# CW_demcheva_ControlBoard_Sh1.net
KiCad netlist of a schematic drawn in Altium Designer
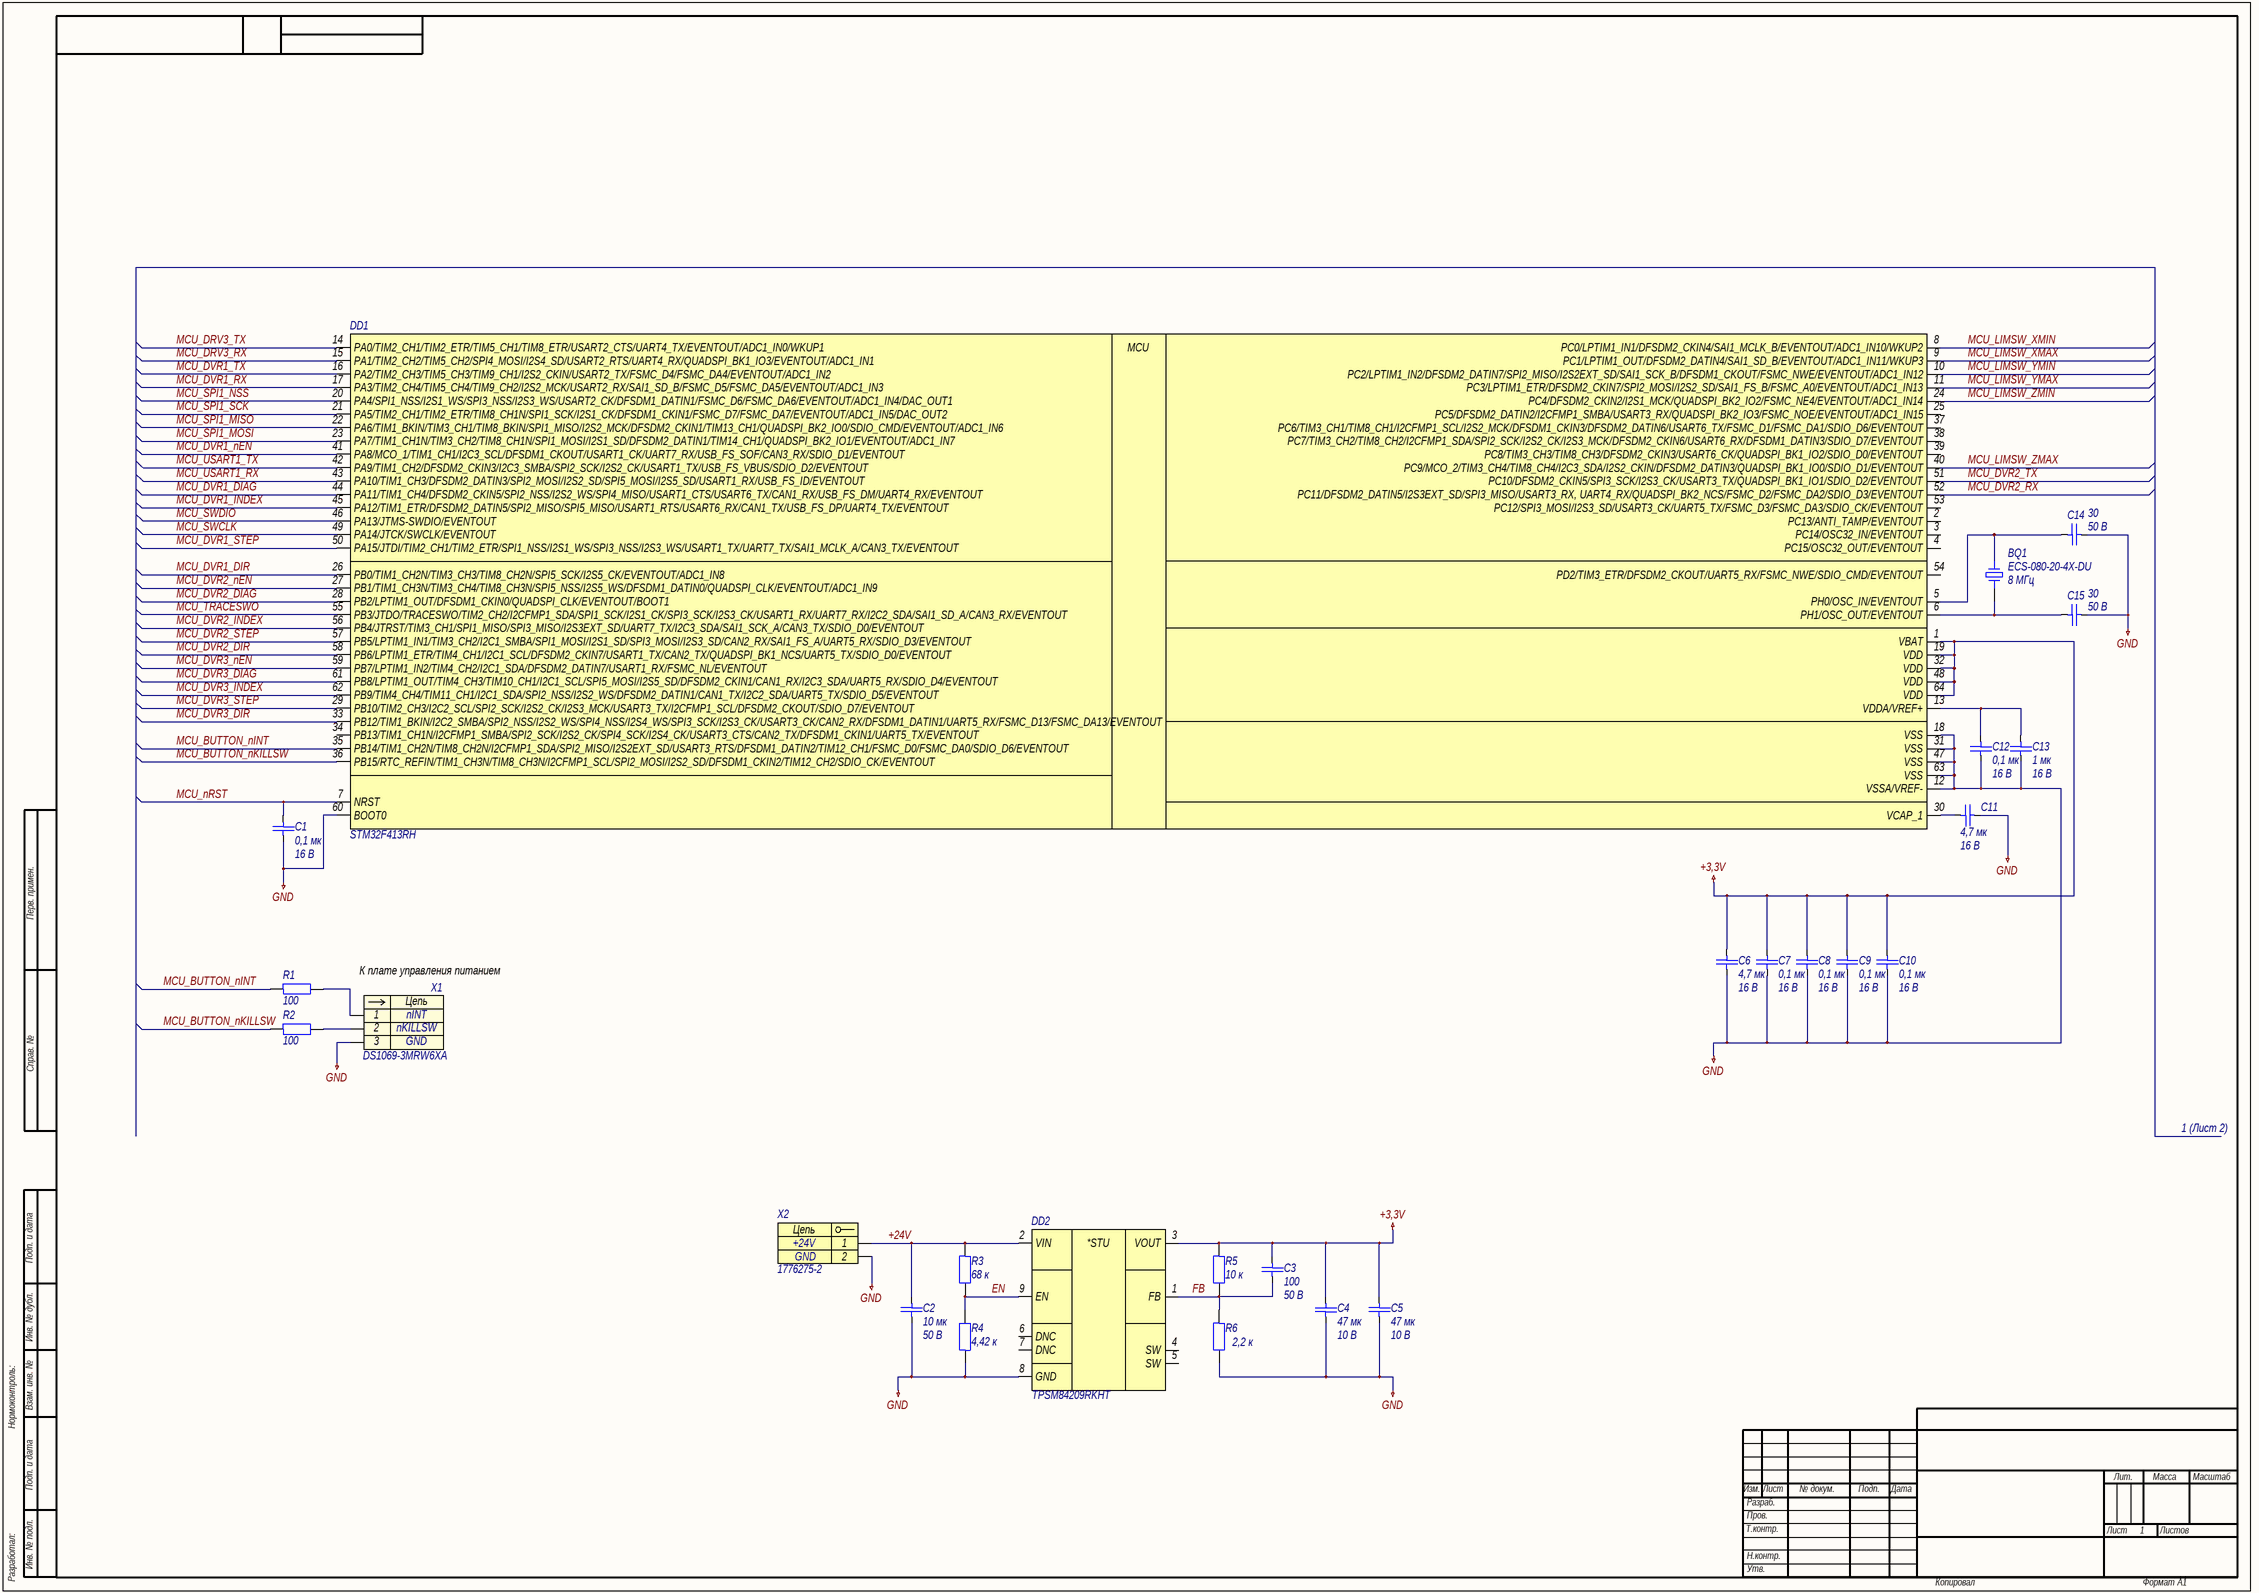
[diagram p0: CW_demcheva_ControlBoard_Sh1.SchDoc]

(export (version "E")
  (design (tool "Eeschema 10.0.6"))
  (components
    (comp (ref "BQ1")
      (value "ECS-080-20-4X-DU")
      (footprint "HC-49/US")
      (description "=Описание")
      (fields (field (name "ЧАСТОТA") "8 МГц"))
      (libsource (lib "Database_Students") (part "RESONATOR-COMMON"))
    )
    (comp (ref "C1")
      (value "0,1 мк")
      (footprint "C0603")
      (description "=Описание")
      (fields (field (name "НАПРЯЖЕНИЕ") "16 В"))
      (libsource (lib "Database_Students") (part "CAPACITOR-NONPOLAR"))
    )
    (comp (ref "C2")
      (value "10 мк")
      (footprint "C0805")
      (description "=Описание")
      (fields (field (name "НАПРЯЖЕНИЕ") "50 В"))
      (libsource (lib "Database_Students") (part "CAPACITOR-NONPOLAR"))
    )
    (comp (ref "C3")
      (value "100")
      (footprint "C0603")
      (description "=Описание")
      (fields (field (name "НАПРЯЖЕНИЕ") "50 В"))
      (libsource (lib "Database_Students") (part "CAPACITOR-NONPOLAR"))
    )
    (comp (ref "C4")
      (value "47 мк")
      (footprint "C0805")
      (description "=Описание")
      (fields (field (name "НАПРЯЖЕНИЕ") "10 В"))
      (libsource (lib "Database_Students") (part "CAPACITOR-NONPOLAR"))
    )
    (comp (ref "C5")
      (value "47 мк")
      (footprint "C0805")
      (description "=Описание")
      (fields (field (name "НАПРЯЖЕНИЕ") "10 В"))
      (libsource (lib "Database_Students") (part "CAPACITOR-NONPOLAR"))
    )
    (comp (ref "C6")
      (value "4,7 мк")
      (footprint "C0805")
      (description "=Описание")
      (fields (field (name "НАПРЯЖЕНИЕ") "16 В"))
      (libsource (lib "Database_Students") (part "CAPACITOR-NONPOLAR"))
    )
    (comp (ref "C7")
      (value "0,1 мк")
      (footprint "C0603")
      (description "=Описание")
      (fields (field (name "НАПРЯЖЕНИЕ") "16 В"))
      (libsource (lib "Database_Students") (part "CAPACITOR-NONPOLAR"))
    )
    (comp (ref "C8")
      (value "0,1 мк")
      (footprint "C0603")
      (description "=Описание")
      (fields (field (name "НАПРЯЖЕНИЕ") "16 В"))
      (libsource (lib "Database_Students") (part "CAPACITOR-NONPOLAR"))
    )
    (comp (ref "C9")
      (value "0,1 мк")
      (footprint "C0603")
      (description "=Описание")
      (fields (field (name "НАПРЯЖЕНИЕ") "16 В"))
      (libsource (lib "Database_Students") (part "CAPACITOR-NONPOLAR"))
    )
    (comp (ref "C10")
      (value "0,1 мк")
      (footprint "C0603")
      (description "=Описание")
      (fields (field (name "НАПРЯЖЕНИЕ") "16 В"))
      (libsource (lib "Database_Students") (part "CAPACITOR-NONPOLAR"))
    )
    (comp (ref "C11")
      (value "4,7 мк")
      (footprint "C0805")
      (description "=Описание")
      (fields (field (name "НАПРЯЖЕНИЕ") "16 В"))
      (libsource (lib "Database_Students") (part "CAPACITOR-NONPOLAR"))
    )
    (comp (ref "C12")
      (value "0,1 мк")
      (footprint "C0603")
      (description "=Описание")
      (fields (field (name "НАПРЯЖЕНИЕ") "16 В"))
      (libsource (lib "Database_Students") (part "CAPACITOR-NONPOLAR"))
    )
    (comp (ref "C13")
      (value "1 мк")
      (footprint "C0603")
      (description "=Описание")
      (fields (field (name "НАПРЯЖЕНИЕ") "16 В"))
      (libsource (lib "Database_Students") (part "CAPACITOR-NONPOLAR"))
    )
    (comp (ref "C14")
      (value "30")
      (footprint "C0603")
      (description "=Описание")
      (fields (field (name "НАПРЯЖЕНИЕ") "50 В"))
      (libsource (lib "Database_Students") (part "CAPACITOR-NONPOLAR"))
    )
    (comp (ref "C15")
      (value "30")
      (footprint "C0603")
      (description "=Описание")
      (fields (field (name "НАПРЯЖЕНИЕ") "50 В"))
      (libsource (lib "Database_Students") (part "CAPACITOR-NONPOLAR"))
    )
    (comp (ref "DD1")
      (value "STM32F413RH")
      (footprint "LQFP-64-P50-1000X1000X160-L60X22")
      (description "=Описание")
      (libsource (lib "Database_Students") (part "STM32F413RHT6"))
    )
    (comp (ref "DD2")
      (value "TPSM84209RKHT")
      (footprint "QFN-FCMOD-9-P65-450X400X210")
      (description "=Описание")
      (libsource (lib "Database_Students") (part "TPSM84209RKHT"))
    )
    (comp (ref "R1")
      (value "100")
      (footprint "R0603")
      (description "=Описание")
      (libsource (lib "Database_Students") (part "RESISTOR-COMMON"))
    )
    (comp (ref "R2")
      (value "100")
      (footprint "R0603")
      (description "=Описание")
      (libsource (lib "Database_Students") (part "RESISTOR-COMMON"))
    )
    (comp (ref "R3")
      (value "68 к")
      (footprint "R0603")
      (description "=Описание")
      (libsource (lib "Database_Students") (part "RESISTOR-COMMON"))
    )
    (comp (ref "R4")
      (value "4,42 к")
      (footprint "R0603")
      (description "=Описание")
      (libsource (lib "Database_Students") (part "RESISTOR-COMMON"))
    )
    (comp (ref "R5")
      (value "10 к")
      (footprint "R0603")
      (description "=Описание")
      (libsource (lib "Database_Students") (part "RESISTOR-COMMON"))
    )
    (comp (ref "R6")
      (value "2,2 к")
      (footprint "R0603")
      (description "=Описание")
      (libsource (lib "Database_Students") (part "RESISTOR-COMMON"))
    )
    (comp (ref "X1")
      (value "DS1069-3MRW6XA")
      (footprint "DS1069-3MRW6XA")
      (description "=Описание")
      (libsource (lib "Database_Students") (part "HEADER-3-PLG"))
    )
    (comp (ref "X2")
      (value "1776275-2")
      (footprint "1776275-2")
      (description "=Описание")
      (libsource (lib "Database_Students") (part "HEADER-2-TRM"))
    )
  )
  (nets
    (net (code "1") (name "+3,3V") (class "Default")
      (node (ref "C10") (pin "2") (pinfunction "2_2") (pintype "passive"))
      (node (ref "C3") (pin "2") (pinfunction "2_2") (pintype "passive"))
      (node (ref "C4") (pin "1") (pinfunction "1_1") (pintype "passive"))
      (node (ref "C5") (pin "2") (pinfunction "2_2") (pintype "passive"))
      (node (ref "C6") (pin "2") (pinfunction "2_2") (pintype "passive"))
      (node (ref "C7") (pin "2") (pinfunction "2_2") (pintype "passive"))
      (node (ref "C8") (pin "2") (pinfunction "2_2") (pintype "passive"))
      (node (ref "C9") (pin "2") (pinfunction "2_2") (pintype "passive"))
      (node (ref "DD1") (pin "1") (pinfunction "VBAT_1") (pintype "passive"))
      (node (ref "DD1") (pin "19") (pinfunction "VDD_19") (pintype "passive"))
      (node (ref "DD1") (pin "32") (pinfunction "VDD_32") (pintype "passive"))
      (node (ref "DD1") (pin "48") (pinfunction "VDD_48") (pintype "passive"))
      (node (ref "DD1") (pin "64") (pinfunction "VDD_64") (pintype "passive"))
      (node (ref "DD2") (pin "3") (pinfunction "VOUT_3") (pintype "passive"))
      (node (ref "R5") (pin "1") (pinfunction "1_1") (pintype "passive"))
    )
    (net (code "2") (name "/+24V") (class "Default")
      (node (ref "C2") (pin "2") (pinfunction "2_2") (pintype "passive"))
      (node (ref "DD2") (pin "2") (pinfunction "VIN_2") (pintype "passive"))
      (node (ref "R3") (pin "1") (pinfunction "1_1") (pintype "passive"))
      (node (ref "X2") (pin "1") (pinfunction "1_1") (pintype "passive"))
    )
    (net (code "3") (name "/EN") (class "Default")
      (node (ref "DD2") (pin "9") (pinfunction "EN_9") (pintype "passive"))
      (node (ref "R3") (pin "2") (pinfunction "2_2") (pintype "passive"))
      (node (ref "R4") (pin "2") (pinfunction "2_2") (pintype "passive"))
    )
    (net (code "4") (name "/FB") (class "Default")
      (node (ref "C3") (pin "1") (pinfunction "1_1") (pintype "passive"))
      (node (ref "DD2") (pin "1") (pinfunction "FB_1") (pintype "passive"))
      (node (ref "R5") (pin "2") (pinfunction "2_2") (pintype "passive"))
      (node (ref "R6") (pin "1") (pinfunction "1_1") (pintype "passive"))
    )
    (net (code "5") (name "/MCU_BUTTON_nINT") (class "Default")
      (node (ref "DD1") (pin "35") (pinfunction "PB14/TIM1_CH2N/TIM8_CH2N/I2CFMP1_SDA/SPI2_MISO/I2S2EXT_SD/USART3_RTS/DFSDM1_DATIN2/TIM12_CH1/FSMC_D0/FSMC_DA0/SDIO_D6/EVENTOUT_35") (pintype "passive"))
      (node (ref "R1") (pin "1") (pinfunction "1_1") (pintype "passive"))
    )
    (net (code "6") (name "/MCU_BUTTON_nKILLSW") (class "Default")
      (node (ref "DD1") (pin "36") (pinfunction "PB15/RTC_REFIN/TIM1_CH3N/TIM8_CH3N/I2CFMP1_SCL/SPI2_MOSI/I2S2_SD/DFSDM1_CKIN2/TIM12_CH2/SDIO_CK/EVENTOUT_36") (pintype "passive"))
      (node (ref "R2") (pin "1") (pinfunction "1_1") (pintype "passive"))
    )
    (net (code "7") (name "/MCU_DRV3_RX") (class "Default")
      (node (ref "DD1") (pin "15") (pinfunction "PA1/TIM2_CH2/TIM5_CH2/SPI4_MOSI/I2S4_SD/USART2_RTS/UART4_RX/QUADSPI_BK1_IO3/EVENTOUT/ADC1_IN1_15") (pintype "passive"))
    )
    (net (code "8") (name "/MCU_DRV3_TX") (class "Default")
      (node (ref "DD1") (pin "14") (pinfunction "PA0/TIM2_CH1/TIM2_ETR/TIM5_CH1/TIM8_ETR/USART2_CTS/UART4_TX/EVENTOUT/ADC1_IN0/WKUP1_14") (pintype "passive"))
    )
    (net (code "9") (name "/MCU_DVR1_DIAG") (class "Default")
      (node (ref "DD1") (pin "44") (pinfunction "PA11/TIM1_CH4/DFSDM2_CKIN5/SPI2_NSS/I2S2_WS/SPI4_MISO/USART1_CTS/USART6_TX/CAN1_RX/USB_FS_DM/UART4_RX/EVENTOUT_44") (pintype "passive"))
    )
    (net (code "10") (name "/MCU_DVR1_DIR") (class "Default")
      (node (ref "DD1") (pin "26") (pinfunction "PB0/TIM1_CH2N/TIM3_CH3/TIM8_CH2N/SPI5_SCK/I2S5_CK/EVENTOUT/ADC1_IN8_26") (pintype "passive"))
    )
    (net (code "11") (name "/MCU_DVR1_INDEX") (class "Default")
      (node (ref "DD1") (pin "45") (pinfunction "PA12/TIM1_ETR/DFSDM2_DATIN5/SPI2_MISO/SPI5_MISO/USART1_RTS/USART6_RX/CAN1_TX/USB_FS_DP/UART4_TX/EVENTOUT_45") (pintype "passive"))
    )
    (net (code "12") (name "/MCU_DVR1_RX") (class "Default")
      (node (ref "DD1") (pin "17") (pinfunction "PA3/TIM2_CH4/TIM5_CH4/TIM9_CH2/I2S2_MCK/USART2_RX/SAI1_SD_B/FSMC_D5/FSMC_DA5/EVENTOUT/ADC1_IN3_17") (pintype "passive"))
    )
    (net (code "13") (name "/MCU_DVR1_STEP") (class "Default")
      (node (ref "DD1") (pin "50") (pinfunction "PA15/JTDI/TIM2_CH1/TIM2_ETR/SPI1_NSS/I2S1_WS/SPI3_NSS/I2S3_WS/USART1_TX/UART7_TX/SAI1_MCLK_A/CAN3_TX/EVENTOUT_50") (pintype "passive"))
    )
    (net (code "14") (name "/MCU_DVR1_TX") (class "Default")
      (node (ref "DD1") (pin "16") (pinfunction "PA2/TIM2_CH3/TIM5_CH3/TIM9_CH1/I2S2_CKIN/USART2_TX/FSMC_D4/FSMC_DA4/EVENTOUT/ADC1_IN2_16") (pintype "passive"))
    )
    (net (code "15") (name "/MCU_DVR1_nEN") (class "Default")
      (node (ref "DD1") (pin "41") (pinfunction "PA8/MCO_1/TIM1_CH1/I2C3_SCL/DFSDM1_CKOUT/USART1_CK/UART7_RX/USB_FS_SOF/CAN3_RX/SDIO_D1/EVENTOUT_41") (pintype "passive"))
    )
    (net (code "16") (name "/MCU_DVR2_DIAG") (class "Default")
      (node (ref "DD1") (pin "28") (pinfunction "PB2/LPTIM1_OUT/DFSDM1_CKIN0/QUADSPI_CLK/EVENTOUT/BOOT1_28") (pintype "passive"))
    )
    (net (code "17") (name "/MCU_DVR2_DIR") (class "Default")
      (node (ref "DD1") (pin "58") (pinfunction "PB6/LPTIM1_ETR/TIM4_CH1/I2C1_SCL/DFSDM2_CKIN7/USART1_TX/CAN2_TX/QUADSPI_BK1_NCS/UART5_TX/SDIO_D0/EVENTOUT_58") (pintype "passive"))
    )
    (net (code "18") (name "/MCU_DVR2_INDEX") (class "Default")
      (node (ref "DD1") (pin "56") (pinfunction "PB4/JTRST/TIM3_CH1/SPI1_MISO/SPI3_MISO/I2S3EXT_SD/UART7_TX/I2C3_SDA/SAI1_SCK_A/CAN3_TX/SDIO_D0/EVENTOUT_56") (pintype "passive"))
    )
    (net (code "19") (name "/MCU_DVR2_RX") (class "Default")
      (node (ref "DD1") (pin "52") (pinfunction "PC11/DFSDM2_DATIN5/I2S3EXT_SD/SPI3_MISO/USART3_RX,_UART4_RX/QUADSPI_BK2_NCS/FSMC_D2/FSMC_DA2/SDIO_D3/EVENTOUT_52") (pintype "passive"))
    )
    (net (code "20") (name "/MCU_DVR2_STEP") (class "Default")
      (node (ref "DD1") (pin "57") (pinfunction "PB5/LPTIM1_IN1/TIM3_CH2/I2C1_SMBA/SPI1_MOSI/I2S1_SD/SPI3_MOSI/I2S3_SD/CAN2_RX/SAI1_FS_A/UART5_RX/SDIO_D3/EVENTOUT_57") (pintype "passive"))
    )
    (net (code "21") (name "/MCU_DVR2_TX") (class "Default")
      (node (ref "DD1") (pin "51") (pinfunction "PC10/DFSDM2_CKIN5/SPI3_SCK/I2S3_CK/USART3_TX/QUADSPI_BK1_IO1/SDIO_D2/EVENTOUT_51") (pintype "passive"))
    )
    (net (code "22") (name "/MCU_DVR2_nEN") (class "Default")
      (node (ref "DD1") (pin "27") (pinfunction "PB1/TIM1_CH3N/TIM3_CH4/TIM8_CH3N/SPI5_NSS/I2S5_WS/DFSDM1_DATIN0/QUADSPI_CLK/EVENTOUT/ADC1_IN9_27") (pintype "passive"))
    )
    (net (code "23") (name "/MCU_DVR3_DIAG") (class "Default")
      (node (ref "DD1") (pin "61") (pinfunction "PB8/LPTIM1_OUT/TIM4_CH3/TIM10_CH1/I2C1_SCL/SPI5_MOSI/I2S5_SD/DFSDM2_CKIN1/CAN1_RX/I2C3_SDA/UART5_RX/SDIO_D4/EVENTOUT_61") (pintype "passive"))
    )
    (net (code "24") (name "/MCU_DVR3_DIR") (class "Default")
      (node (ref "DD1") (pin "33") (pinfunction "PB12/TIM1_BKIN/I2C2_SMBA/SPI2_NSS/I2S2_WS/SPI4_NSS/I2S4_WS/SPI3_SCK/I2S3_CK/USART3_CK/CAN2_RX/DFSDM1_DATIN1/UART5_RX/FSMC_D13/FSMC_DA13/EVENTOUT_33") (pintype "passive"))
    )
    (net (code "25") (name "/MCU_DVR3_INDEX") (class "Default")
      (node (ref "DD1") (pin "62") (pinfunction "PB9/TIM4_CH4/TIM11_CH1/I2C1_SDA/SPI2_NSS/I2S2_WS/DFSDM2_DATIN1/CAN1_TX/I2C2_SDA/UART5_TX/SDIO_D5/EVENTOUT_62") (pintype "passive"))
    )
    (net (code "26") (name "/MCU_DVR3_STEP") (class "Default")
      (node (ref "DD1") (pin "29") (pinfunction "PB10/TIM2_CH3/I2C2_SCL/SPI2_SCK/I2S2_CK/I2S3_MCK/USART3_TX/I2CFMP1_SCL/DFSDM2_CKOUT/SDIO_D7/EVENTOUT_29") (pintype "passive"))
    )
    (net (code "27") (name "/MCU_DVR3_nEN") (class "Default")
      (node (ref "DD1") (pin "59") (pinfunction "PB7/LPTIM1_IN2/TIM4_CH2/I2C1_SDA/DFSDM2_DATIN7/USART1_RX/FSMC_NL/EVENTOUT_59") (pintype "passive"))
    )
    (net (code "28") (name "/MCU_LIMSW_XMAX") (class "Default")
      (node (ref "DD1") (pin "9") (pinfunction "PC1/LPTIM1_OUT/DFSDM2_DATIN4/SAI1_SD_B/EVENTOUT/ADC1_IN11/WKUP3_9") (pintype "passive"))
    )
    (net (code "29") (name "/MCU_LIMSW_XMIN") (class "Default")
      (node (ref "DD1") (pin "8") (pinfunction "PC0/LPTIM1_IN1/DFSDM2_CKIN4/SAI1_MCLK_B/EVENTOUT/ADC1_IN10/WKUP2_8") (pintype "passive"))
    )
    (net (code "30") (name "/MCU_LIMSW_YMAX") (class "Default")
      (node (ref "DD1") (pin "11") (pinfunction "PC3/LPTIM1_ETR/DFSDM2_CKIN7/SPI2_MOSI/I2S2_SD/SAI1_FS_B/FSMC_A0/EVENTOUT/ADC1_IN13_11") (pintype "passive"))
    )
    (net (code "31") (name "/MCU_LIMSW_YMIN") (class "Default")
      (node (ref "DD1") (pin "10") (pinfunction "PC2/LPTIM1_IN2/DFSDM2_DATIN7/SPI2_MISO/I2S2EXT_SD/SAI1_SCK_B/DFSDM1_CKOUT/FSMC_NWE/EVENTOUT/ADC1_IN12_10") (pintype "passive"))
    )
    (net (code "32") (name "/MCU_LIMSW_ZMAX") (class "Default")
      (node (ref "DD1") (pin "40") (pinfunction "PC9/MCO_2/TIM3_CH4/TIM8_CH4/I2C3_SDA/I2S2_CKIN/DFSDM2_DATIN3/QUADSPI_BK1_IO0/SDIO_D1/EVENTOUT_40") (pintype "passive"))
    )
    (net (code "33") (name "/MCU_LIMSW_ZMIN") (class "Default")
      (node (ref "DD1") (pin "24") (pinfunction "PC4/DFSDM2_CKIN2/I2S1_MCK/QUADSPI_BK2_IO2/FSMC_NE4/EVENTOUT/ADC1_IN14_24") (pintype "passive"))
    )
    (net (code "34") (name "/MCU_SPI1_MISO") (class "Default")
      (node (ref "DD1") (pin "22") (pinfunction "PA6/TIM1_BKIN/TIM3_CH1/TIM8_BKIN/SPI1_MISO/I2S2_MCK/DFSDM2_CKIN1/TIM13_CH1/QUADSPI_BK2_IO0/SDIO_CMD/EVENTOUT/ADC1_IN6_22") (pintype "passive"))
    )
    (net (code "35") (name "/MCU_SPI1_MOSI") (class "Default")
      (node (ref "DD1") (pin "23") (pinfunction "PA7/TIM1_CH1N/TIM3_CH2/TIM8_CH1N/SPI1_MOSI/I2S1_SD/DFSDM2_DATIN1/TIM14_CH1/QUADSPI_BK2_IO1/EVENTOUT/ADC1_IN7_23") (pintype "passive"))
    )
    (net (code "36") (name "/MCU_SPI1_NSS") (class "Default")
      (node (ref "DD1") (pin "20") (pinfunction "PA4/SPI1_NSS/I2S1_WS/SPI3_NSS/I2S3_WS/USART2_CK/DFSDM1_DATIN1/FSMC_D6/FSMC_DA6/EVENTOUT/ADC1_IN4/DAC_OUT1_20") (pintype "passive"))
    )
    (net (code "37") (name "/MCU_SPI1_SCK") (class "Default")
      (node (ref "DD1") (pin "21") (pinfunction "PA5/TIM2_CH1/TIM2_ETR/TIM8_CH1N/SPI1_SCK/I2S1_CK/DFSDM1_CKIN1/FSMC_D7/FSMC_DA7/EVENTOUT/ADC1_IN5/DAC_OUT2_21") (pintype "passive"))
    )
    (net (code "38") (name "/MCU_SWCLK") (class "Default")
      (node (ref "DD1") (pin "49") (pinfunction "PA14/JTCK/SWCLK/EVENTOUT_49") (pintype "passive"))
    )
    (net (code "39") (name "/MCU_SWDIO") (class "Default")
      (node (ref "DD1") (pin "46") (pinfunction "PA13/JTMS-SWDIO/EVENTOUT_46") (pintype "passive"))
    )
    (net (code "40") (name "/MCU_TRACESWO") (class "Default")
      (node (ref "DD1") (pin "55") (pinfunction "PB3/JTDO/TRACESWO/TIM2_CH2/I2CFMP1_SDA/SPI1_SCK/I2S1_CK/SPI3_SCK/I2S3_CK/USART1_RX/UART7_RX/I2C2_SDA/SAI1_SD_A/CAN3_RX/EVENTOUT_55") (pintype "passive"))
    )
    (net (code "41") (name "/MCU_USART1_RX") (class "Default")
      (node (ref "DD1") (pin "43") (pinfunction "PA10/TIM1_CH3/DFSDM2_DATIN3/SPI2_MOSI/I2S2_SD/SPI5_MOSI/I2S5_SD/USART1_RX/USB_FS_ID/EVENTOUT_43") (pintype "passive"))
    )
    (net (code "42") (name "/MCU_USART1_TX") (class "Default")
      (node (ref "DD1") (pin "42") (pinfunction "PA9/TIM1_CH2/DFSDM2_CKIN3/I2C3_SMBA/SPI2_SCK/I2S2_CK/USART1_TX/USB_FS_VBUS/SDIO_D2/EVENTOUT_42") (pintype "passive"))
    )
    (net (code "43") (name "/MCU_nRST") (class "Default")
      (node (ref "C1") (pin "2") (pinfunction "2_2") (pintype "passive"))
      (node (ref "DD1") (pin "7") (pinfunction "NRST_7") (pintype "passive"))
    )
    (net (code "44") (name "GND") (class "Default")
      (node (ref "C1") (pin "1") (pinfunction "1_1") (pintype "passive"))
      (node (ref "C10") (pin "1") (pinfunction "1_1") (pintype "passive"))
      (node (ref "C11") (pin "1") (pinfunction "1_1") (pintype "passive"))
      (node (ref "C12") (pin "1") (pinfunction "1_1") (pintype "passive"))
      (node (ref "C13") (pin "1") (pinfunction "1_1") (pintype "passive"))
      (node (ref "C14") (pin "1") (pinfunction "1_1") (pintype "passive"))
      (node (ref "C15") (pin "1") (pinfunction "1_1") (pintype "passive"))
      (node (ref "C2") (pin "1") (pinfunction "1_1") (pintype "passive"))
      (node (ref "C4") (pin "2") (pinfunction "2_2") (pintype "passive"))
      (node (ref "C5") (pin "1") (pinfunction "1_1") (pintype "passive"))
      (node (ref "C6") (pin "1") (pinfunction "1_1") (pintype "passive"))
      (node (ref "C7") (pin "1") (pinfunction "1_1") (pintype "passive"))
      (node (ref "C8") (pin "1") (pinfunction "1_1") (pintype "passive"))
      (node (ref "C9") (pin "1") (pinfunction "1_1") (pintype "passive"))
      (node (ref "DD1") (pin "12") (pinfunction "VSSA/VREF-_12") (pintype "passive"))
      (node (ref "DD1") (pin "18") (pinfunction "VSS_18") (pintype "passive"))
      (node (ref "DD1") (pin "31") (pinfunction "VSS_31") (pintype "passive"))
      (node (ref "DD1") (pin "47") (pinfunction "VSS_47") (pintype "passive"))
      (node (ref "DD1") (pin "60") (pinfunction "BOOT0_60") (pintype "passive"))
      (node (ref "DD1") (pin "63") (pinfunction "VSS_63") (pintype "passive"))
      (node (ref "DD2") (pin "8") (pinfunction "GND_8") (pintype "passive"))
      (node (ref "R4") (pin "1") (pinfunction "1_1") (pintype "passive"))
      (node (ref "R6") (pin "2") (pinfunction "2_2") (pintype "passive"))
      (node (ref "X1") (pin "3") (pinfunction "3_3") (pintype "passive"))
      (node (ref "X2") (pin "2") (pinfunction "2_2") (pintype "passive"))
    )
    (net (code "45") (name "Net-(DD1-PH0{slash}OSC_IN{slash}EVENTOUT)") (class "Default")
      (node (ref "BQ1") (pin "1") (pinfunction "1_1") (pintype "passive"))
      (node (ref "C14") (pin "2") (pinfunction "2_2") (pintype "passive"))
      (node (ref "DD1") (pin "5") (pinfunction "PH0/OSC_IN/EVENTOUT_5") (pintype "passive"))
    )
    (net (code "46") (name "Net-(DD1-PH1{slash}OSC_OUT{slash}EVENTOUT)") (class "Default")
      (node (ref "BQ1") (pin "2") (pinfunction "2_2") (pintype "passive"))
      (node (ref "C15") (pin "2") (pinfunction "2_2") (pintype "passive"))
      (node (ref "DD1") (pin "6") (pinfunction "PH1/OSC_OUT/EVENTOUT_6") (pintype "passive"))
    )
    (net (code "47") (name "Net-(DD1-VCAP_1)") (class "Default")
      (node (ref "C11") (pin "2") (pinfunction "2_2") (pintype "passive"))
      (node (ref "DD1") (pin "30") (pinfunction "VCAP_1_30") (pintype "passive"))
    )
    (net (code "48") (name "Net-(DD1-VDDA{slash}VREF+)") (class "Default")
      (node (ref "C12") (pin "2") (pinfunction "2_2") (pintype "passive"))
      (node (ref "C13") (pin "2") (pinfunction "2_2") (pintype "passive"))
      (node (ref "DD1") (pin "13") (pinfunction "VDDA/VREF+_13") (pintype "passive"))
    )
    (net (code "49") (name "Net-(R1-Pad2)") (class "Default")
      (node (ref "R1") (pin "2") (pinfunction "2_2") (pintype "passive"))
      (node (ref "X1") (pin "1") (pinfunction "1_1") (pintype "passive"))
    )
    (net (code "50") (name "Net-(R2-Pad2)") (class "Default")
      (node (ref "R2") (pin "2") (pinfunction "2_2") (pintype "passive"))
      (node (ref "X1") (pin "2") (pinfunction "2_2") (pintype "passive"))
    )
    (net (code "51") (name "unconnected-(DD1-PB13{slash}TIM1_CH1N{slash}I2CFMP1_SMBA{slash}SPI2_SCK{slash}I2S2_CK{slash}SPI4_SCK{slash}I2S4_CK{slash}USART3_CTS{slash}CAN2_TX{slash}DFSDM1_CKIN1{slash}UART5_TX{slash}EVENTOUT-Pad34)") (class "Default")
      (node (ref "DD1") (pin "34") (pinfunction "PB13/TIM1_CH1N/I2CFMP1_SMBA/SPI2_SCK/I2S2_CK/SPI4_SCK/I2S4_CK/USART3_CTS/CAN2_TX/DFSDM1_CKIN1/UART5_TX/EVENTOUT_34") (pintype "passive"))
    )
    (net (code "52") (name "unconnected-(DD1-PC5{slash}DFSDM2_DATIN2{slash}I2CFMP1_SMBA{slash}USART3_RX{slash}QUADSPI_BK2_IO3{slash}FSMC_NOE{slash}EVENTOUT{slash}ADC1_IN15-Pad25)") (class "Default")
      (node (ref "DD1") (pin "25") (pinfunction "PC5/DFSDM2_DATIN2/I2CFMP1_SMBA/USART3_RX/QUADSPI_BK2_IO3/FSMC_NOE/EVENTOUT/ADC1_IN15_25") (pintype "passive"))
    )
    (net (code "53") (name "unconnected-(DD1-PC6{slash}TIM3_CH1{slash}TIM8_CH1{slash}I2CFMP1_SCL{slash}I2S2_MCK{slash}DFSDM1_CKIN3{slash}DFSDM2_DATIN6{slash}USART6_TX{slash}FSMC_D1{slash}FSMC_DA1{slash}SDIO_D6{slash}EVENTOUT-Pad37)") (class "Default")
      (node (ref "DD1") (pin "37") (pinfunction "PC6/TIM3_CH1/TIM8_CH1/I2CFMP1_SCL/I2S2_MCK/DFSDM1_CKIN3/DFSDM2_DATIN6/USART6_TX/FSMC_D1/FSMC_DA1/SDIO_D6/EVENTOUT_37") (pintype "passive"))
    )
    (net (code "54") (name "unconnected-(DD1-PC7{slash}TIM3_CH2{slash}TIM8_CH2{slash}I2CFMP1_SDA{slash}SPI2_SCK{slash}I2S2_CK{slash}I2S3_MCK{slash}DFSDM2_CKIN6{slash}USART6_RX{slash}DFSDM1_DATIN3{slash}SDIO_D7{slash}EVENTOUT-Pad38)") (class "Default")
      (node (ref "DD1") (pin "38") (pinfunction "PC7/TIM3_CH2/TIM8_CH2/I2CFMP1_SDA/SPI2_SCK/I2S2_CK/I2S3_MCK/DFSDM2_CKIN6/USART6_RX/DFSDM1_DATIN3/SDIO_D7/EVENTOUT_38") (pintype "passive"))
    )
    (net (code "55") (name "unconnected-(DD1-PC8{slash}TIM3_CH3{slash}TIM8_CH3{slash}DFSDM2_CKIN3{slash}USART6_CK{slash}QUADSPI_BK1_IO2{slash}SDIO_D0{slash}EVENTOUT-Pad39)") (class "Default")
      (node (ref "DD1") (pin "39") (pinfunction "PC8/TIM3_CH3/TIM8_CH3/DFSDM2_CKIN3/USART6_CK/QUADSPI_BK1_IO2/SDIO_D0/EVENTOUT_39") (pintype "passive"))
    )
    (net (code "56") (name "unconnected-(DD1-PC12{slash}SPI3_MOSI{slash}I2S3_SD{slash}USART3_CK{slash}UART5_TX{slash}FSMC_D3{slash}FSMC_DA3{slash}SDIO_CK{slash}EVENTOUT-Pad53)") (class "Default")
      (node (ref "DD1") (pin "53") (pinfunction "PC12/SPI3_MOSI/I2S3_SD/USART3_CK/UART5_TX/FSMC_D3/FSMC_DA3/SDIO_CK/EVENTOUT_53") (pintype "passive"))
    )
    (net (code "57") (name "unconnected-(DD1-PC13{slash}ANTI_TAMP{slash}EVENTOUT-Pad2)") (class "Default")
      (node (ref "DD1") (pin "2") (pinfunction "PC13/ANTI_TAMP/EVENTOUT_2") (pintype "passive"))
    )
    (net (code "58") (name "unconnected-(DD1-PC14{slash}OSC32_IN{slash}EVENTOUT-Pad3)") (class "Default")
      (node (ref "DD1") (pin "3") (pinfunction "PC14/OSC32_IN/EVENTOUT_3") (pintype "passive"))
    )
    (net (code "59") (name "unconnected-(DD1-PC15{slash}OSC32_OUT{slash}EVENTOUT-Pad4)") (class "Default")
      (node (ref "DD1") (pin "4") (pinfunction "PC15/OSC32_OUT/EVENTOUT_4") (pintype "passive"))
    )
    (net (code "60") (name "unconnected-(DD1-PD2{slash}TIM3_ETR{slash}DFSDM2_CKOUT{slash}UART5_RX{slash}FSMC_NWE{slash}SDIO_CMD{slash}EVENTOUT-Pad54)") (class "Default")
      (node (ref "DD1") (pin "54") (pinfunction "PD2/TIM3_ETR/DFSDM2_CKOUT/UART5_RX/FSMC_NWE/SDIO_CMD/EVENTOUT_54") (pintype "passive"))
    )
    (net (code "61") (name "unconnected-(DD2-DNC-Pad6)") (class "Default")
      (node (ref "DD2") (pin "6") (pinfunction "DNC_6") (pintype "passive"))
    )
    (net (code "62") (name "unconnected-(DD2-DNC-Pad7)") (class "Default")
      (node (ref "DD2") (pin "7") (pinfunction "DNC_7") (pintype "passive"))
    )
    (net (code "63") (name "unconnected-(DD2-SW-Pad4)") (class "Default")
      (node (ref "DD2") (pin "4") (pinfunction "SW_4") (pintype "passive"))
    )
    (net (code "64") (name "unconnected-(DD2-SW-Pad5)") (class "Default")
      (node (ref "DD2") (pin "5") (pinfunction "SW_5") (pintype "passive"))
    )
  )
)
